# sensor-sm.net
KiCad netlist of a schematic drawn in EAGLE
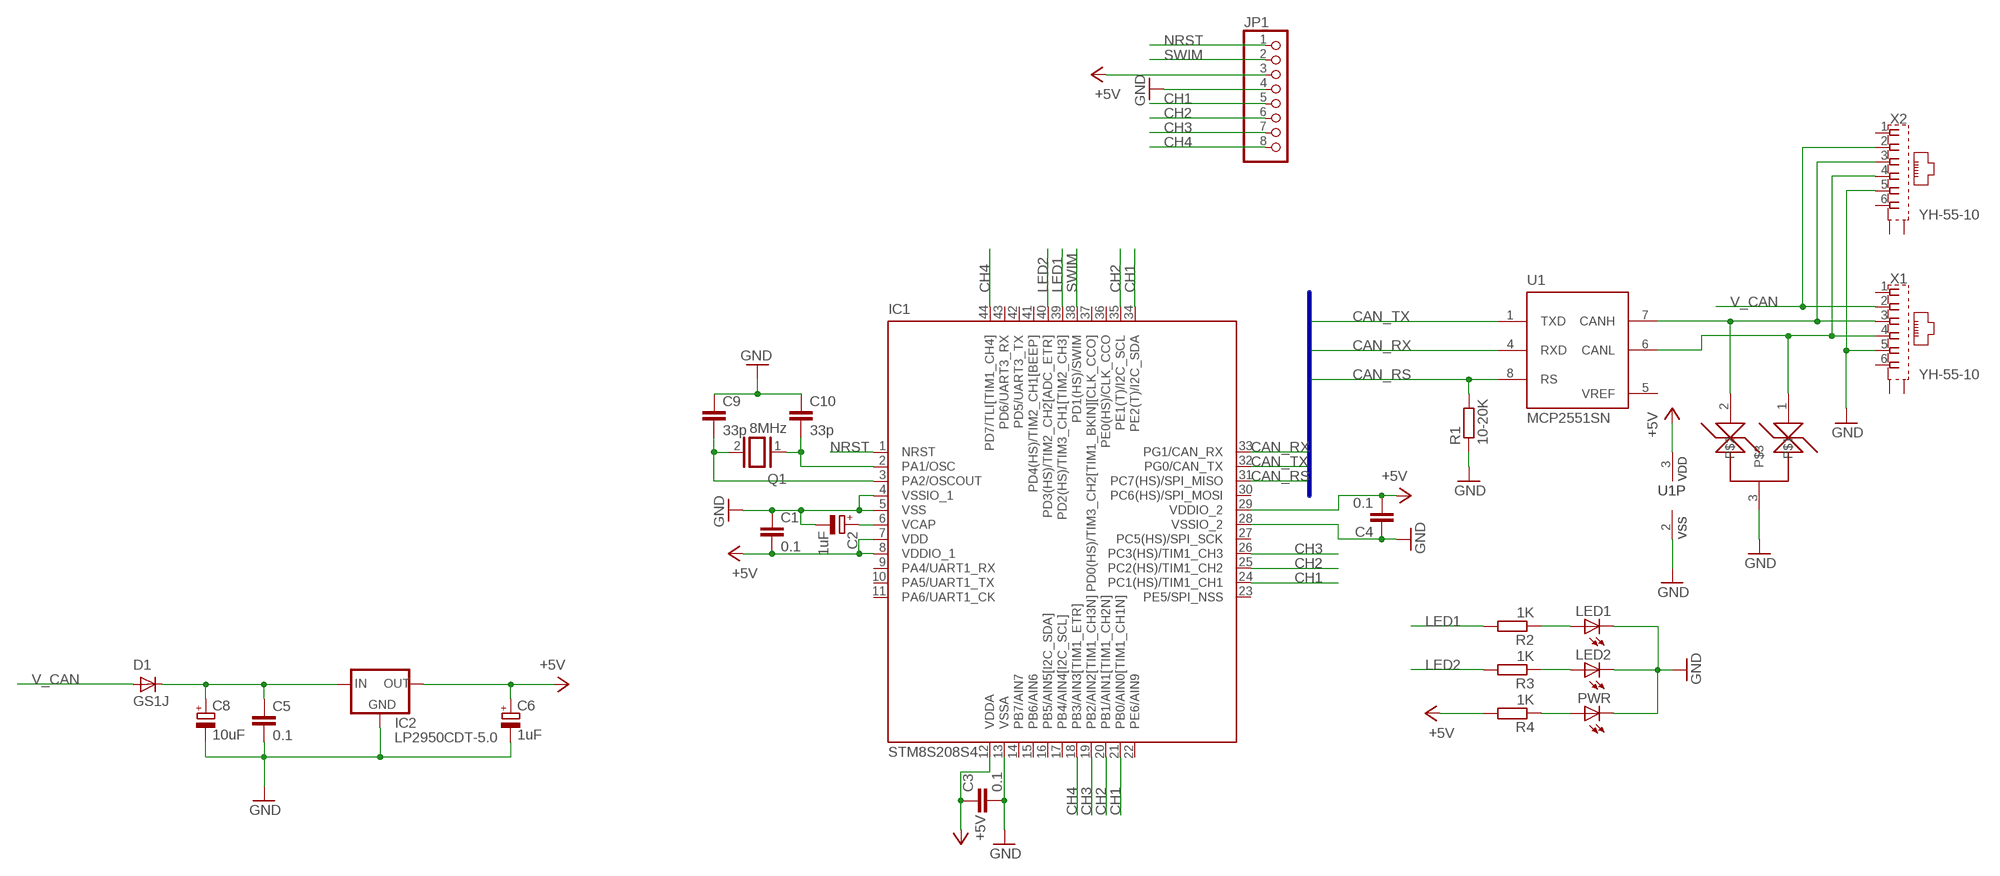
[diagram p0: schematic, sheet 1]

(export (version "E")
  (design (tool "Eeschema 10.0.6"))
  (components
    (comp (ref "C1")
      (value "0.1")
      (footprint "eagle-import:C0805K")
      (libsource (lib "eagle-import") (part "C-EUC0805K"))
    )
    (comp (ref "C2")
      (value "1uF")
      (footprint "eagle-import:E2-4")
      (libsource (lib "eagle-import") (part "CPOL-EUE2-4"))
    )
    (comp (ref "C3")
      (value "0.1")
      (footprint "eagle-import:C0805K")
      (libsource (lib "eagle-import") (part "C-EUC0805K"))
    )
    (comp (ref "C4")
      (value "0.1")
      (footprint "eagle-import:C0805K")
      (libsource (lib "eagle-import") (part "C-EUC0805K"))
    )
    (comp (ref "C5")
      (value "0.1")
      (footprint "eagle-import:C0805K")
      (libsource (lib "eagle-import") (part "C-EUC0805K"))
    )
    (comp (ref "C6")
      (value "1uF")
      (footprint "eagle-import:E2-4")
      (libsource (lib "eagle-import") (part "CPOL-EUE2-4"))
    )
    (comp (ref "C8")
      (value "10uF")
      (footprint "eagle-import:E2-4")
      (libsource (lib "eagle-import") (part "CPOL-EUE2-4"))
    )
    (comp (ref "C9")
      (value "33p")
      (footprint "eagle-import:C0805K")
      (libsource (lib "eagle-import") (part "C-EUC0805K"))
    )
    (comp (ref "C10")
      (value "33p")
      (footprint "eagle-import:C0805K")
      (libsource (lib "eagle-import") (part "C-EUC0805K"))
    )
    (comp (ref "D1")
      (value "GS1J")
      (footprint "eagle-import:SMA-DO214AC")
      (libsource (lib "eagle-import") (part "GF1"))
    )
    (comp (ref "IC1")
      (value "STM8S208S4")
      (footprint "eagle-import:LQFP44-10X10")
      (fields (field (name "MPN") "STM8S208S"))
      (libsource (lib "eagle-import") (part "STM8S208S4"))
    )
    (comp (ref "IC2")
      (value "LP2950CDT-5.0")
      (footprint "eagle-import:DPACK")
      (libsource (lib "eagle-import") (part "LP2950?CDT-5.0"))
    )
    (comp (ref "JP1")
      (value "PINHD-1X8/90")
      (footprint "eagle-import:1X08_90")
      (libsource (lib "eagle-import") (part "PINHD-1X8/90"))
    )
    (comp (ref "LED1")
      (value "LEDSML1206")
      (footprint "eagle-import:SML1206")
      (libsource (lib "eagle-import") (part "LEDSML1206"))
    )
    (comp (ref "LED2")
      (value "LEDSML1206")
      (footprint "eagle-import:SML1206")
      (libsource (lib "eagle-import") (part "LEDSML1206"))
    )
    (comp (ref "NUP2105L")
      (value "NUP2105L")
      (footprint "eagle-import:SOT23")
      (libsource (lib "eagle-import") (part "NUP2105L"))
    )
    (comp (ref "PWR")
      (value "LEDSML1206")
      (footprint "eagle-import:SML1206")
      (libsource (lib "eagle-import") (part "LEDSML1206"))
    )
    (comp (ref "Q1")
      (value "8MHz")
      (footprint "eagle-import:QS")
      (libsource (lib "eagle-import") (part "XTAL/S"))
    )
    (comp (ref "R1")
      (value "10-20K")
      (footprint "eagle-import:R0805")
      (libsource (lib "eagle-import") (part "R-EU_R0805"))
    )
    (comp (ref "R2")
      (value "1K")
      (footprint "eagle-import:R0805")
      (libsource (lib "eagle-import") (part "R-EU_R0805"))
    )
    (comp (ref "R3")
      (value "1K")
      (footprint "eagle-import:R0805")
      (libsource (lib "eagle-import") (part "R-EU_R0805"))
    )
    (comp (ref "R4")
      (value "1K")
      (footprint "eagle-import:R0805")
      (libsource (lib "eagle-import") (part "R-EU_R0805"))
    )
    (comp (ref "U1")
      (value "MCP2551SN")
      (footprint "eagle-import:SO-08")
      (libsource (lib "eagle-import") (part "MCP2551SN"))
    )
    (comp (ref "X1")
      (value "YH-55-10")
      (footprint "eagle-import:YH-55-10")
      (libsource (lib "eagle-import") (part "YH-55-10"))
    )
    (comp (ref "X2")
      (value "YH-55-10")
      (footprint "eagle-import:YH-55-10")
      (libsource (lib "eagle-import") (part "YH-55-10"))
    )
  )
  (nets
    (net (code "1") (name "+5V") (class "Default")
      (node (ref "C1") (pin "2") (pinfunction "2_2") (pintype "passive"))
      (node (ref "C3") (pin "1") (pinfunction "1_1") (pintype "passive"))
      (node (ref "C4") (pin "2") (pinfunction "2_2") (pintype "passive"))
      (node (ref "C6") (pin "+") (pinfunction "+_+") (pintype "passive"))
      (node (ref "IC1") (pin "12") (pinfunction "VDDA_12") (pintype "power_in"))
      (node (ref "IC1") (pin "29") (pinfunction "VDDIO_2_29") (pintype "power_in"))
      (node (ref "IC1") (pin "7") (pinfunction "VDD_7") (pintype "power_in"))
      (node (ref "IC1") (pin "8") (pinfunction "VDDIO_1_8") (pintype "power_in"))
      (node (ref "IC2") (pin "3") (pinfunction "OUT_3") (pintype "passive"))
      (node (ref "JP1") (pin "3") (pinfunction "3_3") (pintype "passive"))
      (node (ref "R4") (pin "2") (pinfunction "2_2") (pintype "passive"))
      (node (ref "U1") (pin "3") (pinfunction "VDD_3") (pintype "power_in"))
    )
    (net (code "2") (name "/CAN_RS") (class "Default")
      (node (ref "IC1") (pin "31") (pinfunction "PC7(HS)/SPI_MISO_31") (pintype "bidirectional"))
      (node (ref "R1") (pin "2") (pinfunction "2_2") (pintype "passive"))
      (node (ref "U1") (pin "8") (pinfunction "RS_8") (pintype "input"))
    )
    (net (code "3") (name "/CAN_RX") (class "Default")
      (node (ref "IC1") (pin "33") (pinfunction "PG1/CAN_RX_33") (pintype "bidirectional"))
      (node (ref "U1") (pin "4") (pinfunction "RXD_4") (pintype "output"))
    )
    (net (code "4") (name "/CAN_TX") (class "Default")
      (node (ref "IC1") (pin "32") (pinfunction "PG0/CAN_TX_32") (pintype "bidirectional"))
      (node (ref "U1") (pin "1") (pinfunction "TXD_1") (pintype "input"))
    )
    (net (code "5") (name "/CH1") (class "Default")
      (node (ref "IC1") (pin "21") (pinfunction "PB0/AIN0[TIM1_CH1N]_21") (pintype "bidirectional"))
      (node (ref "IC1") (pin "24") (pinfunction "PC1(HS)/TIM1_CH1_24") (pintype "bidirectional"))
      (node (ref "IC1") (pin "34") (pinfunction "PE2(T)/I2C_SDA_34") (pintype "bidirectional"))
      (node (ref "JP1") (pin "5") (pinfunction "5_5") (pintype "passive"))
    )
    (net (code "6") (name "/CH2") (class "Default")
      (node (ref "IC1") (pin "20") (pinfunction "PB1/AIN1[TIM1_CH2N]_20") (pintype "bidirectional"))
      (node (ref "IC1") (pin "25") (pinfunction "PC2(HS)/TIM1_CH2_25") (pintype "bidirectional"))
      (node (ref "IC1") (pin "35") (pinfunction "PE1(T)/I2C_SCL_35") (pintype "bidirectional"))
      (node (ref "JP1") (pin "6") (pinfunction "6_6") (pintype "passive"))
    )
    (net (code "7") (name "/CH3") (class "Default")
      (node (ref "IC1") (pin "19") (pinfunction "PB2/AIN2[TIM1_CH3N]_19") (pintype "bidirectional"))
      (node (ref "IC1") (pin "26") (pinfunction "PC3(HS)/TIM1_CH3_26") (pintype "bidirectional"))
      (node (ref "JP1") (pin "7") (pinfunction "7_7") (pintype "passive"))
    )
    (net (code "8") (name "/CH4") (class "Default")
      (node (ref "IC1") (pin "18") (pinfunction "PB3/AIN3[TIM1_ETR]_18") (pintype "bidirectional"))
      (node (ref "IC1") (pin "44") (pinfunction "PD7/TLI[TIM1_CH4]_44") (pintype "bidirectional"))
      (node (ref "JP1") (pin "8") (pinfunction "8_8") (pintype "passive"))
    )
    (net (code "9") (name "/LED1") (class "Default")
      (node (ref "IC1") (pin "39") (pinfunction "PD2(HS)/TIM3_CH1[TIM2_CH3]_39") (pintype "bidirectional"))
      (node (ref "R2") (pin "2") (pinfunction "2_2") (pintype "passive"))
    )
    (net (code "10") (name "/LED2") (class "Default")
      (node (ref "IC1") (pin "40") (pinfunction "PD3(HS)/TIM2_CH2[ADC_ETR]_40") (pintype "bidirectional"))
      (node (ref "R3") (pin "2") (pinfunction "2_2") (pintype "passive"))
    )
    (net (code "11") (name "/NRST") (class "Default")
      (node (ref "IC1") (pin "1") (pinfunction "NRST_1") (pintype "bidirectional"))
      (node (ref "JP1") (pin "1") (pinfunction "1_1") (pintype "passive"))
    )
    (net (code "12") (name "/SWIM") (class "Default")
      (node (ref "IC1") (pin "38") (pinfunction "PD1(HS)/SWIM_38") (pintype "bidirectional"))
      (node (ref "JP1") (pin "2") (pinfunction "2_2") (pintype "passive"))
    )
    (net (code "13") (name "/VREF") (class "Default")
      (node (ref "U1") (pin "5") (pinfunction "VREF_5") (pintype "power_in"))
    )
    (net (code "14") (name "/V_CAN") (class "Default")
      (node (ref "D1") (pin "A") (pinfunction "A_A") (pintype "passive"))
      (node (ref "X1") (pin "2") (pinfunction "2_2") (pintype "passive"))
      (node (ref "X2") (pin "2") (pinfunction "2_2") (pintype "passive"))
    )
    (net (code "15") (name "GND") (class "Default")
      (node (ref "C1") (pin "1") (pinfunction "1_1") (pintype "passive"))
      (node (ref "C10") (pin "1") (pinfunction "1_1") (pintype "passive"))
      (node (ref "C2") (pin "-") (pinfunction "-_-") (pintype "passive"))
      (node (ref "C3") (pin "2") (pinfunction "2_2") (pintype "passive"))
      (node (ref "C4") (pin "1") (pinfunction "1_1") (pintype "passive"))
      (node (ref "C5") (pin "2") (pinfunction "2_2") (pintype "passive"))
      (node (ref "C6") (pin "-") (pinfunction "-_-") (pintype "passive"))
      (node (ref "C8") (pin "-") (pinfunction "-_-") (pintype "passive"))
      (node (ref "C9") (pin "1") (pinfunction "1_1") (pintype "passive"))
      (node (ref "IC1") (pin "13") (pinfunction "VSSA_13") (pintype "power_in"))
      (node (ref "IC1") (pin "28") (pinfunction "VSSIO_2_28") (pintype "power_in"))
      (node (ref "IC1") (pin "4") (pinfunction "VSSIO_1_4") (pintype "power_in"))
      (node (ref "IC1") (pin "5") (pinfunction "VSS_5") (pintype "power_in"))
      (node (ref "IC2") (pin "4") (pinfunction "GND_4") (pintype "input"))
      (node (ref "JP1") (pin "4") (pinfunction "4_4") (pintype "passive"))
      (node (ref "LED1") (pin "C") (pinfunction "C_C") (pintype "passive"))
      (node (ref "LED2") (pin "C") (pinfunction "C_C") (pintype "passive"))
      (node (ref "NUP2105L") (pin "3") (pinfunction "P$3_3") (pintype "bidirectional"))
      (node (ref "PWR") (pin "C") (pinfunction "C_C") (pintype "passive"))
      (node (ref "R1") (pin "1") (pinfunction "1_1") (pintype "passive"))
      (node (ref "U1") (pin "2") (pinfunction "VSS_2") (pintype "power_in"))
      (node (ref "X1") (pin "5") (pinfunction "5_5") (pintype "passive"))
      (node (ref "X2") (pin "5") (pinfunction "5_5") (pintype "passive"))
    )
    (net (code "16") (name "Net-(D1-C)") (class "Default")
      (node (ref "C5") (pin "1") (pinfunction "1_1") (pintype "passive"))
      (node (ref "C8") (pin "+") (pinfunction "+_+") (pintype "passive"))
      (node (ref "D1") (pin "K") (pinfunction "C_K") (pintype "passive"))
      (node (ref "IC2") (pin "1") (pinfunction "IN_1") (pintype "input"))
    )
    (net (code "17") (name "Net-(IC1-PA1{slash}OSC)") (class "Default")
      (node (ref "C10") (pin "2") (pinfunction "2_2") (pintype "passive"))
      (node (ref "IC1") (pin "2") (pinfunction "PA1/OSC_2") (pintype "bidirectional"))
      (node (ref "Q1") (pin "1") (pinfunction "1_1") (pintype "passive"))
    )
    (net (code "18") (name "Net-(IC1-PA2{slash}OSCOUT)") (class "Default")
      (node (ref "C9") (pin "2") (pinfunction "2_2") (pintype "passive"))
      (node (ref "IC1") (pin "3") (pinfunction "PA2/OSCOUT_3") (pintype "bidirectional"))
      (node (ref "Q1") (pin "2") (pinfunction "2_2") (pintype "passive"))
    )
    (net (code "19") (name "Net-(IC1-VCAP)") (class "Default")
      (node (ref "C2") (pin "+") (pinfunction "+_+") (pintype "passive"))
      (node (ref "IC1") (pin "6") (pinfunction "VCAP_6") (pintype "power_in"))
    )
    (net (code "20") (name "Net-(LED1-PadA)") (class "Default")
      (node (ref "LED1") (pin "A") (pinfunction "A_A") (pintype "passive"))
      (node (ref "R2") (pin "1") (pinfunction "1_1") (pintype "passive"))
    )
    (net (code "21") (name "Net-(LED2-PadA)") (class "Default")
      (node (ref "LED2") (pin "A") (pinfunction "A_A") (pintype "passive"))
      (node (ref "R3") (pin "1") (pinfunction "1_1") (pintype "passive"))
    )
    (net (code "22") (name "Net-(NUP2105L-P$1)") (class "Default")
      (node (ref "NUP2105L") (pin "1") (pinfunction "P$1_1") (pintype "bidirectional"))
      (node (ref "U1") (pin "6") (pinfunction "CANL_6") (pintype "bidirectional"))
      (node (ref "X1") (pin "4") (pinfunction "4_4") (pintype "passive"))
      (node (ref "X2") (pin "4") (pinfunction "4_4") (pintype "passive"))
    )
    (net (code "23") (name "Net-(NUP2105L-P$2)") (class "Default")
      (node (ref "NUP2105L") (pin "2") (pinfunction "P$2_2") (pintype "bidirectional"))
      (node (ref "U1") (pin "7") (pinfunction "CANH_7") (pintype "bidirectional"))
      (node (ref "X1") (pin "3") (pinfunction "3_3") (pintype "passive"))
      (node (ref "X2") (pin "3") (pinfunction "3_3") (pintype "passive"))
    )
    (net (code "24") (name "Net-(PWR-PadA)") (class "Default")
      (node (ref "PWR") (pin "A") (pinfunction "A_A") (pintype "passive"))
      (node (ref "R4") (pin "1") (pinfunction "1_1") (pintype "passive"))
    )
    (net (code "25") (name "unconnected-(IC1-PA4{slash}UART1_RX-Pad9)") (class "Default")
      (node (ref "IC1") (pin "9") (pinfunction "PA4/UART1_RX_9") (pintype "bidirectional"))
    )
    (net (code "26") (name "unconnected-(IC1-PA5{slash}UART1_TX-Pad10)") (class "Default")
      (node (ref "IC1") (pin "10") (pinfunction "PA5/UART1_TX_10") (pintype "bidirectional"))
    )
    (net (code "27") (name "unconnected-(IC1-PA6{slash}UART1_CK-Pad11)") (class "Default")
      (node (ref "IC1") (pin "11") (pinfunction "PA6/UART1_CK_11") (pintype "bidirectional"))
    )
    (net (code "28") (name "unconnected-(IC1-PB4{slash}AIN4[I2C_SCL]-Pad17)") (class "Default")
      (node (ref "IC1") (pin "17") (pinfunction "PB4/AIN4[I2C_SCL]_17") (pintype "bidirectional"))
    )
    (net (code "29") (name "unconnected-(IC1-PB5{slash}AIN5[I2C_SDA]-Pad16)") (class "Default")
      (node (ref "IC1") (pin "16") (pinfunction "PB5/AIN5[I2C_SDA]_16") (pintype "bidirectional"))
    )
    (net (code "30") (name "unconnected-(IC1-PB6{slash}AIN6-Pad15)") (class "Default")
      (node (ref "IC1") (pin "15") (pinfunction "PB6/AIN6_15") (pintype "bidirectional"))
    )
    (net (code "31") (name "unconnected-(IC1-PB7{slash}AIN7-Pad14)") (class "Default")
      (node (ref "IC1") (pin "14") (pinfunction "PB7/AIN7_14") (pintype "bidirectional"))
    )
    (net (code "32") (name "unconnected-(IC1-PC5(HS){slash}SPI_SCK-Pad27)") (class "Default")
      (node (ref "IC1") (pin "27") (pinfunction "PC5(HS)/SPI_SCK_27") (pintype "bidirectional"))
    )
    (net (code "33") (name "unconnected-(IC1-PC6(HS){slash}SPI_MOSI-Pad30)") (class "Default")
      (node (ref "IC1") (pin "30") (pinfunction "PC6(HS)/SPI_MOSI_30") (pintype "bidirectional"))
    )
    (net (code "34") (name "unconnected-(IC1-PD0(HS){slash}TIM3_CH2[TIM1_BKIN][CLK_CCO]-Pad37)") (class "Default")
      (node (ref "IC1") (pin "37") (pinfunction "PD0(HS)/TIM3_CH2[TIM1_BKIN][CLK_CCO]_37") (pintype "bidirectional"))
    )
    (net (code "35") (name "unconnected-(IC1-PD4(HS){slash}TIM2_CH1[BEEP]-Pad41)") (class "Default")
      (node (ref "IC1") (pin "41") (pinfunction "PD4(HS)/TIM2_CH1[BEEP]_41") (pintype "bidirectional"))
    )
    (net (code "36") (name "unconnected-(IC1-PD5{slash}UART3_TX-Pad42)") (class "Default")
      (node (ref "IC1") (pin "42") (pinfunction "PD5/UART3_TX_42") (pintype "bidirectional"))
    )
    (net (code "37") (name "unconnected-(IC1-PD6{slash}UART3_RX-Pad43)") (class "Default")
      (node (ref "IC1") (pin "43") (pinfunction "PD6/UART3_RX_43") (pintype "bidirectional"))
    )
    (net (code "38") (name "unconnected-(IC1-PE0(HS){slash}CLK_CCO-Pad36)") (class "Default")
      (node (ref "IC1") (pin "36") (pinfunction "PE0(HS)/CLK_CCO_36") (pintype "bidirectional"))
    )
    (net (code "39") (name "unconnected-(IC1-PE5{slash}SPI_NSS-Pad23)") (class "Default")
      (node (ref "IC1") (pin "23") (pinfunction "PE5/SPI_NSS_23") (pintype "bidirectional"))
    )
    (net (code "40") (name "unconnected-(IC1-PE6{slash}AIN9-Pad22)") (class "Default")
      (node (ref "IC1") (pin "22") (pinfunction "PE6/AIN9_22") (pintype "bidirectional"))
    )
    (net (code "41") (name "unconnected-(X1-Pad1)") (class "Default")
      (node (ref "X1") (pin "1") (pinfunction "1_1") (pintype "passive"))
    )
    (net (code "42") (name "unconnected-(X1-Pad6)") (class "Default")
      (node (ref "X1") (pin "6") (pinfunction "6_6") (pintype "passive"))
    )
    (net (code "43") (name "unconnected-(X1-S-PadS1)") (class "Default")
      (node (ref "X1") (pin "S1") (pinfunction "S_S1") (pintype "passive"))
    )
    (net (code "44") (name "unconnected-(X1-S-PadS2)") (class "Default")
      (node (ref "X1") (pin "S2") (pinfunction "S_S2") (pintype "passive"))
    )
    (net (code "45") (name "unconnected-(X2-Pad1)") (class "Default")
      (node (ref "X2") (pin "1") (pinfunction "1_1") (pintype "passive"))
    )
    (net (code "46") (name "unconnected-(X2-Pad6)") (class "Default")
      (node (ref "X2") (pin "6") (pinfunction "6_6") (pintype "passive"))
    )
    (net (code "47") (name "unconnected-(X2-S-PadS1)") (class "Default")
      (node (ref "X2") (pin "S1") (pinfunction "S_S1") (pintype "passive"))
    )
    (net (code "48") (name "unconnected-(X2-S-PadS2)") (class "Default")
      (node (ref "X2") (pin "S2") (pinfunction "S_S2") (pintype "passive"))
    )
  )
)
